# atmega1284_oled_v2.net
KiCad netlist of a schematic drawn in EAGLE
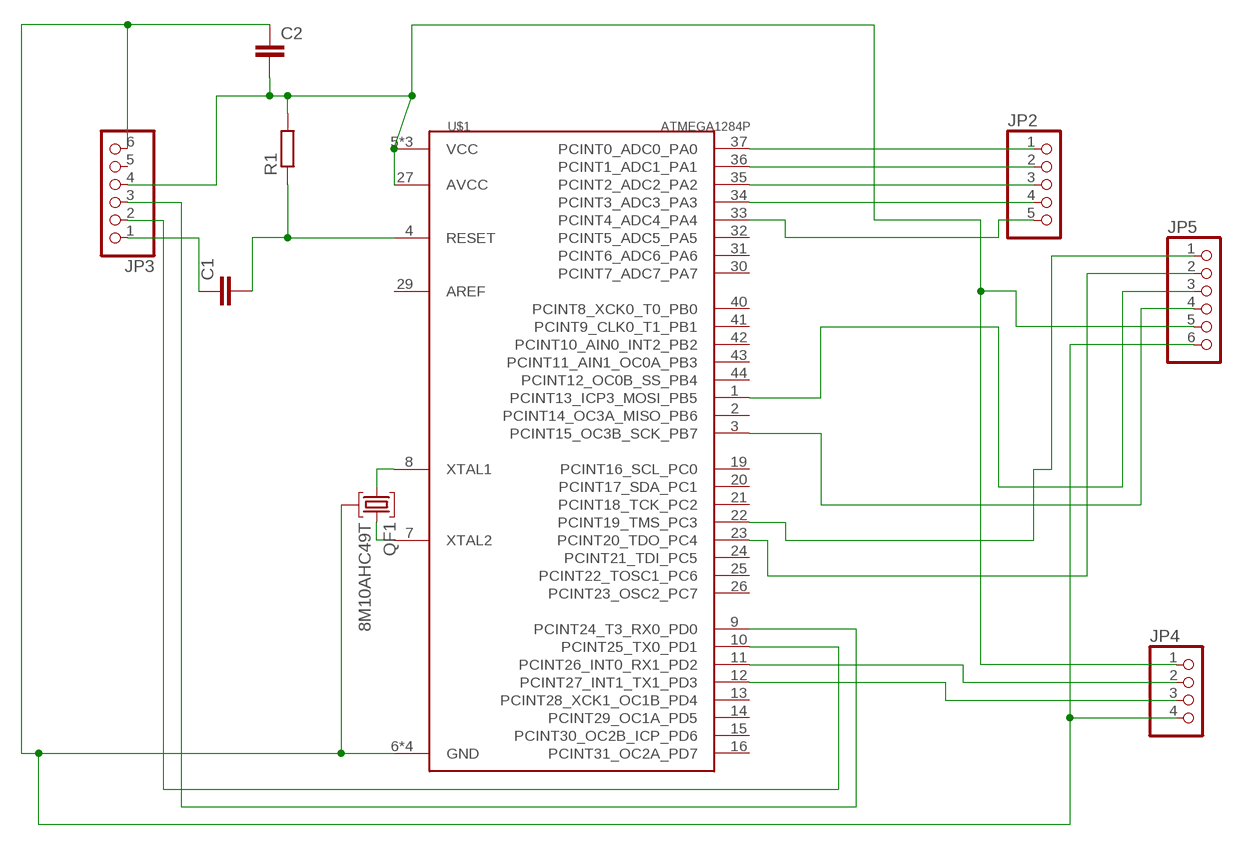
[diagram p0: schematic, sheet 1]

(export (version "E")
  (design (tool "Eeschema 10.0.6"))
  (components
    (comp (ref "C1")
      (value "C-EUC0805")
      (footprint "eagle-import:C0805")
      (libsource (lib "eagle-import") (part "C-EUC0805"))
    )
    (comp (ref "C2")
      (value "C-EUC0805")
      (footprint "eagle-import:C0805")
      (libsource (lib "eagle-import") (part "C-EUC0805"))
    )
    (comp (ref "JP2")
      (value "PINHD-1X5")
      (footprint "eagle-import:1X05")
      (libsource (lib "eagle-import") (part "PINHD-1X5"))
    )
    (comp (ref "JP3")
      (value "PINHD-1X6")
      (footprint "eagle-import:1X06")
      (libsource (lib "eagle-import") (part "PINHD-1X6"))
    )
    (comp (ref "JP4")
      (value "PINHD-1X4")
      (footprint "eagle-import:1X04")
      (libsource (lib "eagle-import") (part "PINHD-1X4"))
    )
    (comp (ref "JP5")
      (value "PINHD-1X6")
      (footprint "eagle-import:1X06")
      (libsource (lib "eagle-import") (part "PINHD-1X6"))
    )
    (comp (ref "QF1")
      (value "8M10AHC49T")
      (footprint "eagle-import:HC49U")
      (libsource (lib "eagle-import") (part "8M10AHC49T"))
    )
    (comp (ref "R1")
      (value "R-EU_R0805")
      (footprint "eagle-import:R0805")
      (libsource (lib "eagle-import") (part "R-EU_R0805"))
    )
    (comp (ref "U$1")
      (value "ATMEGA1284P")
      (footprint "eagle-import:TQFP44")
      (libsource (lib "eagle-import") (part "ATMEGA1284P"))
    )
  )
  (nets
    (net (code "1") (name "Net-(C1-Pad1)") (class "Default")
      (node (ref "C1") (pin "1") (pinfunction "1_1") (pintype "passive"))
      (node (ref "JP3") (pin "1") (pinfunction "1_1") (pintype "passive"))
    )
    (net (code "2") (name "Net-(C2-Pad1)") (class "Default")
      (node (ref "C2") (pin "1") (pinfunction "1_1") (pintype "passive"))
      (node (ref "JP3") (pin "6") (pinfunction "6_6") (pintype "passive"))
      (node (ref "JP4") (pin "4") (pinfunction "4_4") (pintype "passive"))
      (node (ref "JP5") (pin "6") (pinfunction "6_6") (pintype "passive"))
      (node (ref "QF1") (pin "2") (pinfunction "2_2") (pintype "passive"))
      (node (ref "U$1") (pin "18") (pinfunction "GND_18") (pintype "bidirectional"))
      (node (ref "U$1") (pin "28") (pinfunction "GND_28") (pintype "bidirectional"))
      (node (ref "U$1") (pin "39") (pinfunction "GND_39") (pintype "bidirectional"))
      (node (ref "U$1") (pin "6") (pinfunction "GND_6") (pintype "bidirectional"))
    )
    (net (code "3") (name "Net-(U$1-AVCC)") (class "Default")
      (node (ref "C2") (pin "2") (pinfunction "2_2") (pintype "passive"))
      (node (ref "JP3") (pin "4") (pinfunction "4_4") (pintype "passive"))
      (node (ref "JP4") (pin "1") (pinfunction "1_1") (pintype "passive"))
      (node (ref "JP5") (pin "5") (pinfunction "5_5") (pintype "passive"))
      (node (ref "R1") (pin "2") (pinfunction "2_2") (pintype "passive"))
      (node (ref "U$1") (pin "17") (pinfunction "VCC_17") (pintype "bidirectional"))
      (node (ref "U$1") (pin "27") (pinfunction "AVCC_27") (pintype "bidirectional"))
      (node (ref "U$1") (pin "38") (pinfunction "VCC_38") (pintype "bidirectional"))
      (node (ref "U$1") (pin "5") (pinfunction "VCC_5") (pintype "bidirectional"))
    )
    (net (code "4") (name "Net-(U$1-PCINT0_ADC0_PA0)") (class "Default")
      (node (ref "JP2") (pin "1") (pinfunction "1_1") (pintype "passive"))
      (node (ref "U$1") (pin "37") (pinfunction "PCINT0_ADC0_PA0_37") (pintype "bidirectional"))
    )
    (net (code "5") (name "Net-(U$1-PCINT1_ADC1_PA1)") (class "Default")
      (node (ref "JP2") (pin "2") (pinfunction "2_2") (pintype "passive"))
      (node (ref "U$1") (pin "36") (pinfunction "PCINT1_ADC1_PA1_36") (pintype "bidirectional"))
    )
    (net (code "6") (name "Net-(U$1-PCINT2_ADC2_PA2)") (class "Default")
      (node (ref "JP2") (pin "3") (pinfunction "3_3") (pintype "passive"))
      (node (ref "U$1") (pin "35") (pinfunction "PCINT2_ADC2_PA2_35") (pintype "bidirectional"))
    )
    (net (code "7") (name "Net-(U$1-PCINT3_ADC3_PA3)") (class "Default")
      (node (ref "JP2") (pin "4") (pinfunction "4_4") (pintype "passive"))
      (node (ref "U$1") (pin "34") (pinfunction "PCINT3_ADC3_PA3_34") (pintype "bidirectional"))
    )
    (net (code "8") (name "Net-(U$1-PCINT4_ADC4_PA4)") (class "Default")
      (node (ref "JP2") (pin "5") (pinfunction "5_5") (pintype "passive"))
      (node (ref "U$1") (pin "33") (pinfunction "PCINT4_ADC4_PA4_33") (pintype "bidirectional"))
    )
    (net (code "9") (name "Net-(U$1-PCINT13_ICP3_MOSI_PB5)") (class "Default")
      (node (ref "JP5") (pin "3") (pinfunction "3_3") (pintype "passive"))
      (node (ref "U$1") (pin "1") (pinfunction "PCINT13_ICP3_MOSI_PB5_1") (pintype "bidirectional"))
    )
    (net (code "10") (name "Net-(U$1-PCINT15_OC3B_SCK_PB7)") (class "Default")
      (node (ref "JP5") (pin "4") (pinfunction "4_4") (pintype "passive"))
      (node (ref "U$1") (pin "3") (pinfunction "PCINT15_OC3B_SCK_PB7_3") (pintype "bidirectional"))
    )
    (net (code "11") (name "Net-(U$1-PCINT19_TMS_PC3)") (class "Default")
      (node (ref "JP5") (pin "1") (pinfunction "1_1") (pintype "passive"))
      (node (ref "U$1") (pin "22") (pinfunction "PCINT19_TMS_PC3_22") (pintype "bidirectional"))
    )
    (net (code "12") (name "Net-(U$1-PCINT20_TDO_PC4)") (class "Default")
      (node (ref "JP5") (pin "2") (pinfunction "2_2") (pintype "passive"))
      (node (ref "U$1") (pin "23") (pinfunction "PCINT20_TDO_PC4_23") (pintype "bidirectional"))
    )
    (net (code "13") (name "Net-(U$1-PCINT24_T3_RX0_PD0)") (class "Default")
      (node (ref "JP3") (pin "3") (pinfunction "3_3") (pintype "passive"))
      (node (ref "U$1") (pin "9") (pinfunction "PCINT24_T3_RX0_PD0_9") (pintype "bidirectional"))
    )
    (net (code "14") (name "Net-(U$1-PCINT25_TX0_PD1)") (class "Default")
      (node (ref "JP3") (pin "2") (pinfunction "2_2") (pintype "passive"))
      (node (ref "U$1") (pin "10") (pinfunction "PCINT25_TX0_PD1_10") (pintype "bidirectional"))
    )
    (net (code "15") (name "Net-(U$1-PCINT26_INT0_RX1_PD2)") (class "Default")
      (node (ref "JP4") (pin "2") (pinfunction "2_2") (pintype "passive"))
      (node (ref "U$1") (pin "11") (pinfunction "PCINT26_INT0_RX1_PD2_11") (pintype "bidirectional"))
    )
    (net (code "16") (name "Net-(U$1-PCINT27_INT1_TX1_PD3)") (class "Default")
      (node (ref "JP4") (pin "3") (pinfunction "3_3") (pintype "passive"))
      (node (ref "U$1") (pin "12") (pinfunction "PCINT27_INT1_TX1_PD3_12") (pintype "bidirectional"))
    )
    (net (code "17") (name "Net-(U$1-RESET)") (class "Default")
      (node (ref "C1") (pin "2") (pinfunction "2_2") (pintype "passive"))
      (node (ref "R1") (pin "1") (pinfunction "1_1") (pintype "passive"))
      (node (ref "U$1") (pin "4") (pinfunction "RESET_4") (pintype "bidirectional"))
    )
    (net (code "18") (name "Net-(U$1-XTAL1)") (class "Default")
      (node (ref "QF1") (pin "1") (pinfunction "1_1") (pintype "passive"))
      (node (ref "U$1") (pin "8") (pinfunction "XTAL1_8") (pintype "bidirectional"))
    )
    (net (code "19") (name "Net-(U$1-XTAL2)") (class "Default")
      (node (ref "QF1") (pin "3") (pinfunction "3_3") (pintype "passive"))
      (node (ref "U$1") (pin "7") (pinfunction "XTAL2_7") (pintype "bidirectional"))
    )
    (net (code "20") (name "unconnected-(JP3-Pad5)") (class "Default")
      (node (ref "JP3") (pin "5") (pinfunction "5_5") (pintype "passive"))
    )
    (net (code "21") (name "unconnected-(U$1-AREF-Pad29)") (class "Default")
      (node (ref "U$1") (pin "29") (pinfunction "AREF_29") (pintype "bidirectional"))
    )
    (net (code "22") (name "unconnected-(U$1-PCINT5_ADC5_PA5-Pad32)") (class "Default")
      (node (ref "U$1") (pin "32") (pinfunction "PCINT5_ADC5_PA5_32") (pintype "bidirectional"))
    )
    (net (code "23") (name "unconnected-(U$1-PCINT6_ADC6_PA6-Pad31)") (class "Default")
      (node (ref "U$1") (pin "31") (pinfunction "PCINT6_ADC6_PA6_31") (pintype "bidirectional"))
    )
    (net (code "24") (name "unconnected-(U$1-PCINT7_ADC7_PA7-Pad30)") (class "Default")
      (node (ref "U$1") (pin "30") (pinfunction "PCINT7_ADC7_PA7_30") (pintype "bidirectional"))
    )
    (net (code "25") (name "unconnected-(U$1-PCINT8_XCK0_T0_PB0-Pad40)") (class "Default")
      (node (ref "U$1") (pin "40") (pinfunction "PCINT8_XCK0_T0_PB0_40") (pintype "bidirectional"))
    )
    (net (code "26") (name "unconnected-(U$1-PCINT9_CLK0_T1_PB1-Pad41)") (class "Default")
      (node (ref "U$1") (pin "41") (pinfunction "PCINT9_CLK0_T1_PB1_41") (pintype "bidirectional"))
    )
    (net (code "27") (name "unconnected-(U$1-PCINT10_AIN0_INT2_PB2-Pad42)") (class "Default")
      (node (ref "U$1") (pin "42") (pinfunction "PCINT10_AIN0_INT2_PB2_42") (pintype "bidirectional"))
    )
    (net (code "28") (name "unconnected-(U$1-PCINT11_AIN1_OC0A_PB3-Pad43)") (class "Default")
      (node (ref "U$1") (pin "43") (pinfunction "PCINT11_AIN1_OC0A_PB3_43") (pintype "bidirectional"))
    )
    (net (code "29") (name "unconnected-(U$1-PCINT12_OC0B_SS_PB4-Pad44)") (class "Default")
      (node (ref "U$1") (pin "44") (pinfunction "PCINT12_OC0B_SS_PB4_44") (pintype "bidirectional"))
    )
    (net (code "30") (name "unconnected-(U$1-PCINT14_OC3A_MISO_PB6-Pad2)") (class "Default")
      (node (ref "U$1") (pin "2") (pinfunction "PCINT14_OC3A_MISO_PB6_2") (pintype "bidirectional"))
    )
    (net (code "31") (name "unconnected-(U$1-PCINT16_SCL_PC0-Pad19)") (class "Default")
      (node (ref "U$1") (pin "19") (pinfunction "PCINT16_SCL_PC0_19") (pintype "bidirectional"))
    )
    (net (code "32") (name "unconnected-(U$1-PCINT17_SDA_PC1-Pad20)") (class "Default")
      (node (ref "U$1") (pin "20") (pinfunction "PCINT17_SDA_PC1_20") (pintype "bidirectional"))
    )
    (net (code "33") (name "unconnected-(U$1-PCINT18_TCK_PC2-Pad21)") (class "Default")
      (node (ref "U$1") (pin "21") (pinfunction "PCINT18_TCK_PC2_21") (pintype "bidirectional"))
    )
    (net (code "34") (name "unconnected-(U$1-PCINT21_TDI_PC5-Pad24)") (class "Default")
      (node (ref "U$1") (pin "24") (pinfunction "PCINT21_TDI_PC5_24") (pintype "bidirectional"))
    )
    (net (code "35") (name "unconnected-(U$1-PCINT22_TOSC1_PC6-Pad25)") (class "Default")
      (node (ref "U$1") (pin "25") (pinfunction "PCINT22_TOSC1_PC6_25") (pintype "bidirectional"))
    )
    (net (code "36") (name "unconnected-(U$1-PCINT23_OSC2_PC7-Pad26)") (class "Default")
      (node (ref "U$1") (pin "26") (pinfunction "PCINT23_OSC2_PC7_26") (pintype "bidirectional"))
    )
    (net (code "37") (name "unconnected-(U$1-PCINT28_XCK1_OC1B_PD4-Pad13)") (class "Default")
      (node (ref "U$1") (pin "13") (pinfunction "PCINT28_XCK1_OC1B_PD4_13") (pintype "bidirectional"))
    )
    (net (code "38") (name "unconnected-(U$1-PCINT29_OC1A_PD5-Pad14)") (class "Default")
      (node (ref "U$1") (pin "14") (pinfunction "PCINT29_OC1A_PD5_14") (pintype "bidirectional"))
    )
    (net (code "39") (name "unconnected-(U$1-PCINT30_OC2B_ICP_PD6-Pad15)") (class "Default")
      (node (ref "U$1") (pin "15") (pinfunction "PCINT30_OC2B_ICP_PD6_15") (pintype "bidirectional"))
    )
    (net (code "40") (name "unconnected-(U$1-PCINT31_OC2A_PD7-Pad16)") (class "Default")
      (node (ref "U$1") (pin "16") (pinfunction "PCINT31_OC2A_PD7_16") (pintype "bidirectional"))
    )
  )
)
